# Buck-to-5V.net
KiCad netlist of a schematic drawn in Altium Designer
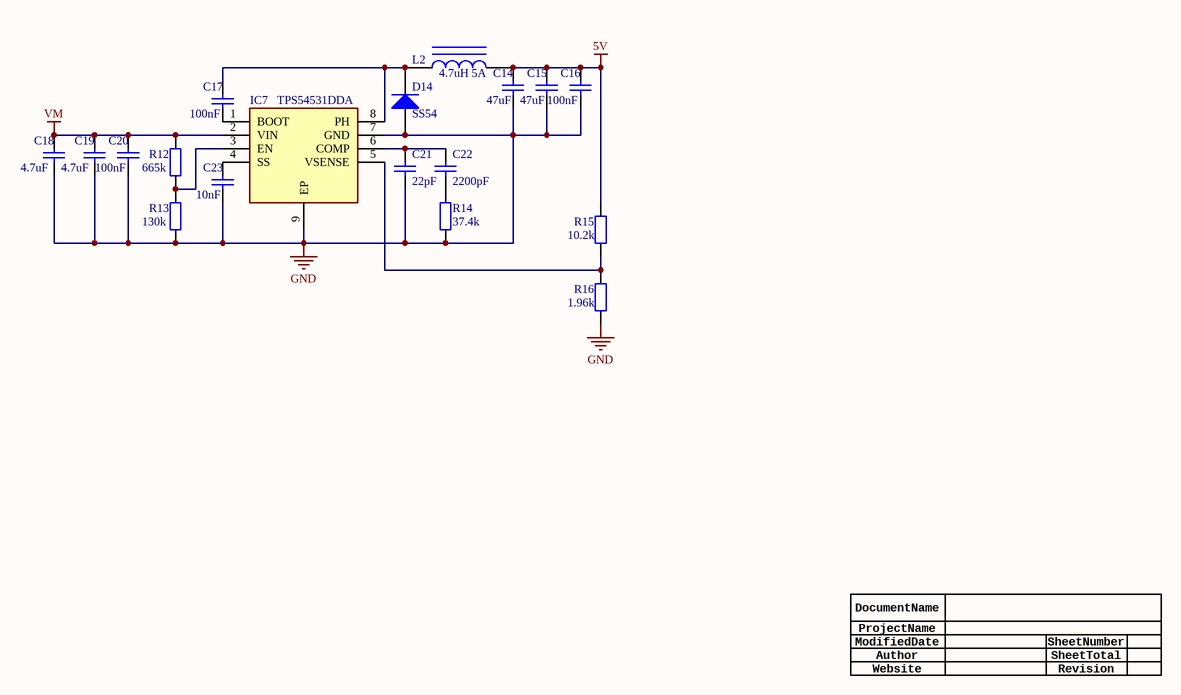
[diagram p0: Buck-to-5V.SchDoc]

(export (version "E")
  (design (tool "Eeschema 10.0.6"))
  (components
    (comp (ref "C14")
      (value "47uF")
      (footprint "CAP-0603")
      (description "贴片电容")
      (libsource (lib "Power_Lib_Altium") (part "CAP"))
    )
    (comp (ref "C15")
      (value "47uF")
      (footprint "CAP-0603")
      (description "贴片电容")
      (libsource (lib "Power_Lib_Altium") (part "CAP"))
    )
    (comp (ref "C16")
      (value "100nF")
      (footprint "CAP-0603")
      (description "贴片电容")
      (libsource (lib "Power_Lib_Altium") (part "CAP"))
    )
    (comp (ref "C17")
      (value "100nF")
      (footprint "CAP-0603")
      (description "贴片电容")
      (libsource (lib "Power_Lib_Altium") (part "CAP"))
    )
    (comp (ref "C18")
      (value "4.7uF")
      (footprint "CAP-0603")
      (description "贴片电容")
      (libsource (lib "Power_Lib_Altium") (part "CAP"))
    )
    (comp (ref "C19")
      (value "4.7uF")
      (footprint "CAP-0603")
      (description "贴片电容")
      (libsource (lib "Power_Lib_Altium") (part "CAP"))
    )
    (comp (ref "C20")
      (value "100nF")
      (footprint "CAP-0603")
      (description "贴片电容")
      (libsource (lib "Power_Lib_Altium") (part "CAP"))
    )
    (comp (ref "C21")
      (value "22pF")
      (footprint "CAP-0603")
      (description "贴片电容")
      (libsource (lib "Power_Lib_Altium") (part "CAP"))
    )
    (comp (ref "C22")
      (value "2200pF")
      (footprint "CAP-0603")
      (description "贴片电容")
      (libsource (lib "Power_Lib_Altium") (part "CAP"))
    )
    (comp (ref "C23")
      (value "10nF")
      (footprint "CAP-0603")
      (description "贴片电容")
      (libsource (lib "Power_Lib_Altium") (part "CAP"))
    )
    (comp (ref "D14")
      (value "SS54")
      (footprint "DO-214AA/SMB")
      (description "肖特基二极管")
      (libsource (lib "Power_Lib_Altium") (part "DIODE"))
    )
    (comp (ref "IC7")
      (value "TPS54531DDA")
      (footprint "SOIC_8_PAD")
      (description "集成稳压芯片")
      (fields (field (name "MOUSER PART NUMBER") "595-TPS54531DDA"))
      (libsource (lib "Power_Lib_Altium") (part "TPS54531DDA"))
    )
    (comp (ref "L2")
      (value "4.7uH 5A")
      (footprint "L-10040")
      (description "电感")
      (libsource (lib "Power_Lib_Altium") (part "INDUCTOR"))
    )
    (comp (ref "R12")
      (value "665k")
      (footprint "R-0603")
      (description "贴片电阻")
      (libsource (lib "Power_Lib_Altium") (part "RES"))
    )
    (comp (ref "R13")
      (value "130k")
      (footprint "R-0603")
      (description "贴片电阻")
      (libsource (lib "Power_Lib_Altium") (part "RES"))
    )
    (comp (ref "R14")
      (value "37.4k")
      (footprint "R-0603")
      (description "贴片电阻")
      (libsource (lib "Power_Lib_Altium") (part "RES"))
    )
    (comp (ref "R15")
      (value "10.2k")
      (footprint "R-0603")
      (description "贴片电阻")
      (libsource (lib "Power_Lib_Altium") (part "RES"))
    )
    (comp (ref "R16")
      (value "1.96k")
      (footprint "R-0603")
      (description "贴片电阻")
      (libsource (lib "Power_Lib_Altium") (part "RES"))
    )
  )
  (nets
    (net (code "1") (name "5V") (class "Default")
      (node (ref "C14") (pin "2") (pinfunction "2_2") (pintype "passive"))
      (node (ref "C15") (pin "2") (pinfunction "2_2") (pintype "passive"))
      (node (ref "C16") (pin "2") (pinfunction "2_2") (pintype "passive"))
      (node (ref "L2") (pin "2") (pinfunction "2_2") (pintype "passive"))
      (node (ref "R15") (pin "2") (pinfunction "2_2") (pintype "passive"))
    )
    (net (code "2") (name "GND") (class "Default")
      (node (ref "C14") (pin "1") (pinfunction "1_1") (pintype "passive"))
      (node (ref "C15") (pin "1") (pinfunction "1_1") (pintype "passive"))
      (node (ref "C16") (pin "1") (pinfunction "1_1") (pintype "passive"))
      (node (ref "C18") (pin "1") (pinfunction "1_1") (pintype "passive"))
      (node (ref "C19") (pin "1") (pinfunction "1_1") (pintype "passive"))
      (node (ref "C20") (pin "1") (pinfunction "1_1") (pintype "passive"))
      (node (ref "C21") (pin "1") (pinfunction "1_1") (pintype "passive"))
      (node (ref "C23") (pin "1") (pinfunction "1_1") (pintype "passive"))
      (node (ref "D14") (pin "1") (pinfunction "A_1") (pintype "passive"))
      (node (ref "IC7") (pin "7") (pinfunction "GND_7") (pintype "passive"))
      (node (ref "IC7") (pin "9") (pinfunction "EP_9") (pintype "passive"))
      (node (ref "R13") (pin "1") (pinfunction "1_1") (pintype "passive"))
      (node (ref "R14") (pin "1") (pinfunction "1_1") (pintype "passive"))
      (node (ref "R16") (pin "1") (pinfunction "1_1") (pintype "passive"))
    )
    (net (code "3") (name "Net-(C22-Pad1)") (class "Default")
      (node (ref "C22") (pin "1") (pinfunction "1_1") (pintype "passive"))
      (node (ref "R14") (pin "2") (pinfunction "2_2") (pintype "passive"))
    )
    (net (code "4") (name "Net-(D14-K)") (class "Default")
      (node (ref "C17") (pin "2") (pinfunction "2_2") (pintype "passive"))
      (node (ref "D14") (pin "2") (pinfunction "K_2") (pintype "passive"))
      (node (ref "IC7") (pin "8") (pinfunction "PH_8") (pintype "passive"))
      (node (ref "L2") (pin "1") (pinfunction "1_1") (pintype "passive"))
    )
    (net (code "5") (name "Net-(IC7-BOOT)") (class "Default")
      (node (ref "C17") (pin "1") (pinfunction "1_1") (pintype "passive"))
      (node (ref "IC7") (pin "1") (pinfunction "BOOT_1") (pintype "passive"))
    )
    (net (code "6") (name "Net-(IC7-COMP)") (class "Default")
      (node (ref "C21") (pin "2") (pinfunction "2_2") (pintype "passive"))
      (node (ref "C22") (pin "2") (pinfunction "2_2") (pintype "passive"))
      (node (ref "IC7") (pin "6") (pinfunction "COMP_6") (pintype "passive"))
    )
    (net (code "7") (name "Net-(IC7-EN)") (class "Default")
      (node (ref "IC7") (pin "3") (pinfunction "EN_3") (pintype "passive"))
      (node (ref "R12") (pin "1") (pinfunction "1_1") (pintype "passive"))
      (node (ref "R13") (pin "2") (pinfunction "2_2") (pintype "passive"))
    )
    (net (code "8") (name "Net-(IC7-SS)") (class "Default")
      (node (ref "C23") (pin "2") (pinfunction "2_2") (pintype "passive"))
      (node (ref "IC7") (pin "4") (pinfunction "SS_4") (pintype "passive"))
    )
    (net (code "9") (name "Net-(IC7-VSENSE)") (class "Default")
      (node (ref "IC7") (pin "5") (pinfunction "VSENSE_5") (pintype "passive"))
      (node (ref "R15") (pin "1") (pinfunction "1_1") (pintype "passive"))
      (node (ref "R16") (pin "2") (pinfunction "2_2") (pintype "passive"))
    )
    (net (code "10") (name "VM") (class "Default")
      (node (ref "C18") (pin "2") (pinfunction "2_2") (pintype "passive"))
      (node (ref "C19") (pin "2") (pinfunction "2_2") (pintype "passive"))
      (node (ref "C20") (pin "2") (pinfunction "2_2") (pintype "passive"))
      (node (ref "IC7") (pin "2") (pinfunction "VIN_2") (pintype "passive"))
      (node (ref "R12") (pin "2") (pinfunction "2_2") (pintype "passive"))
    )
  )
)
